# Sheet1.net
KiCad netlist of a schematic drawn in Altium Designer
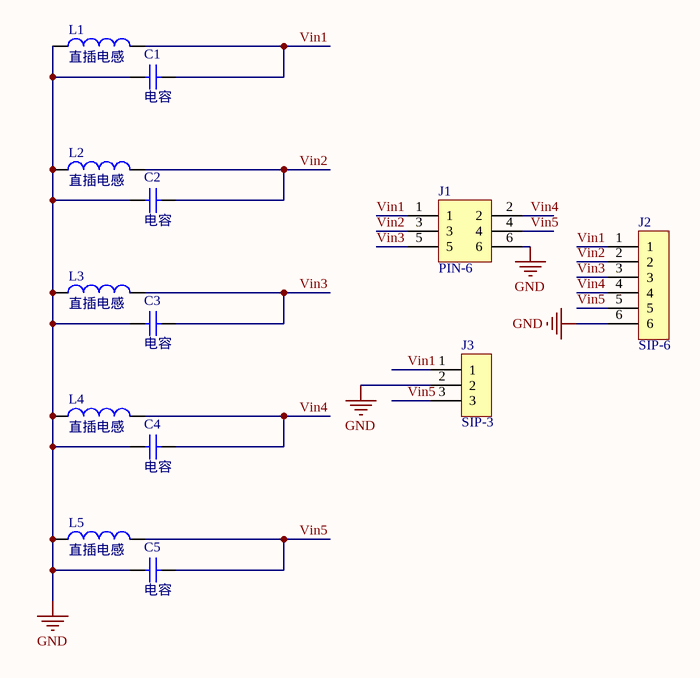
[diagram p0: Sheet1.SchDoc]

(export (version "E")
  (design (tool "Eeschema 10.0.6"))
  (components
    (comp (ref "C1")
      (value "电容")
      (footprint "5mm")
      (description "Capacitor")
      (fields (field (name "PUBLISHER") "Altium Limited"))
      (libsource (lib "容阻感") (part "电容"))
    )
    (comp (ref "C2")
      (value "电容")
      (footprint "5mm")
      (description "Capacitor")
      (fields (field (name "PUBLISHER") "Altium Limited"))
      (libsource (lib "容阻感") (part "电容"))
    )
    (comp (ref "C3")
      (value "电容")
      (footprint "5mm")
      (description "Capacitor")
      (fields (field (name "PUBLISHER") "Altium Limited"))
      (libsource (lib "容阻感") (part "电容"))
    )
    (comp (ref "C4")
      (value "电容")
      (footprint "5mm")
      (description "Capacitor")
      (fields (field (name "PUBLISHER") "Altium Limited"))
      (libsource (lib "容阻感") (part "电容"))
    )
    (comp (ref "C5")
      (value "电容")
      (footprint "5mm")
      (description "Capacitor")
      (fields (field (name "PUBLISHER") "Altium Limited"))
      (libsource (lib "容阻感") (part "电容"))
    )
    (comp (ref "J1") (value "PIN-6") (footprint "2.54简易牛角座6P") (libsource (lib "接插件") (part "PIN-6")))
    (comp (ref "J2") (value "SIP-6") (footprint "2.54排针1X6") (libsource (lib "接插件") (part "SIP-6")))
    (comp (ref "J3") (value "SIP-3") (footprint "XH2.54-3SMD") (libsource (lib "接插件") (part "SIP-3")))
    (comp (ref "L1") (value "直插电感") (footprint "L8*10_4p_L") (libsource (lib "容阻感") (part "直插电感")))
    (comp (ref "L2") (value "直插电感") (footprint "L8*10_4p_L") (libsource (lib "容阻感") (part "直插电感")))
    (comp (ref "L3") (value "直插电感") (footprint "L8*10_4p_C") (libsource (lib "容阻感") (part "直插电感")))
    (comp (ref "L4") (value "直插电感") (footprint "L8*10_4p_R") (libsource (lib "容阻感") (part "直插电感")))
    (comp (ref "L5") (value "直插电感") (footprint "L8*10_4p_R") (libsource (lib "容阻感") (part "直插电感")))
  )
  (nets
    (net (code "1") (name "/Vin1") (class "Default")
      (node (ref "C1") (pin "2") (pinfunction "2_2") (pintype "passive"))
      (node (ref "J1") (pin "1") (pinfunction "1_1") (pintype "passive"))
      (node (ref "J2") (pin "1") (pinfunction "1_1") (pintype "passive"))
      (node (ref "J3") (pin "1") (pinfunction "1_1") (pintype "passive"))
      (node (ref "L1") (pin "2") (pinfunction "2_2") (pintype "passive"))
    )
    (net (code "2") (name "/Vin2") (class "Default")
      (node (ref "C2") (pin "2") (pinfunction "2_2") (pintype "passive"))
      (node (ref "J1") (pin "3") (pinfunction "3_3") (pintype "passive"))
      (node (ref "J2") (pin "2") (pinfunction "2_2") (pintype "passive"))
      (node (ref "L2") (pin "2") (pinfunction "2_2") (pintype "passive"))
    )
    (net (code "3") (name "/Vin3") (class "Default")
      (node (ref "C3") (pin "2") (pinfunction "2_2") (pintype "passive"))
      (node (ref "J1") (pin "5") (pinfunction "5_5") (pintype "passive"))
      (node (ref "J2") (pin "3") (pinfunction "3_3") (pintype "passive"))
      (node (ref "L3") (pin "2") (pinfunction "2_2") (pintype "passive"))
    )
    (net (code "4") (name "/Vin4") (class "Default")
      (node (ref "C4") (pin "2") (pinfunction "2_2") (pintype "passive"))
      (node (ref "J1") (pin "2") (pinfunction "2_2") (pintype "passive"))
      (node (ref "J2") (pin "4") (pinfunction "4_4") (pintype "passive"))
      (node (ref "L4") (pin "2") (pinfunction "2_2") (pintype "passive"))
    )
    (net (code "5") (name "/Vin5") (class "Default")
      (node (ref "C5") (pin "2") (pinfunction "2_2") (pintype "passive"))
      (node (ref "J1") (pin "4") (pinfunction "4_4") (pintype "passive"))
      (node (ref "J2") (pin "5") (pinfunction "5_5") (pintype "passive"))
      (node (ref "J3") (pin "3") (pinfunction "3_3") (pintype "passive"))
      (node (ref "L5") (pin "2") (pinfunction "2_2") (pintype "passive"))
    )
    (net (code "6") (name "GND") (class "Default")
      (node (ref "C1") (pin "1") (pinfunction "1_1") (pintype "passive"))
      (node (ref "C2") (pin "1") (pinfunction "1_1") (pintype "passive"))
      (node (ref "C3") (pin "1") (pinfunction "1_1") (pintype "passive"))
      (node (ref "C4") (pin "1") (pinfunction "1_1") (pintype "passive"))
      (node (ref "C5") (pin "1") (pinfunction "1_1") (pintype "passive"))
      (node (ref "J1") (pin "6") (pinfunction "6_6") (pintype "passive"))
      (node (ref "J2") (pin "6") (pinfunction "6_6") (pintype "passive"))
      (node (ref "J3") (pin "2") (pinfunction "2_2") (pintype "passive"))
      (node (ref "L1") (pin "1") (pinfunction "1_1") (pintype "passive"))
      (node (ref "L2") (pin "1") (pinfunction "1_1") (pintype "passive"))
      (node (ref "L3") (pin "1") (pinfunction "1_1") (pintype "passive"))
      (node (ref "L4") (pin "1") (pinfunction "1_1") (pintype "passive"))
      (node (ref "L5") (pin "1") (pinfunction "1_1") (pintype "passive"))
    )
  )
)
